# NOR_Flash_Storage_Module.net
KiCad netlist of a schematic drawn in EasyEDA
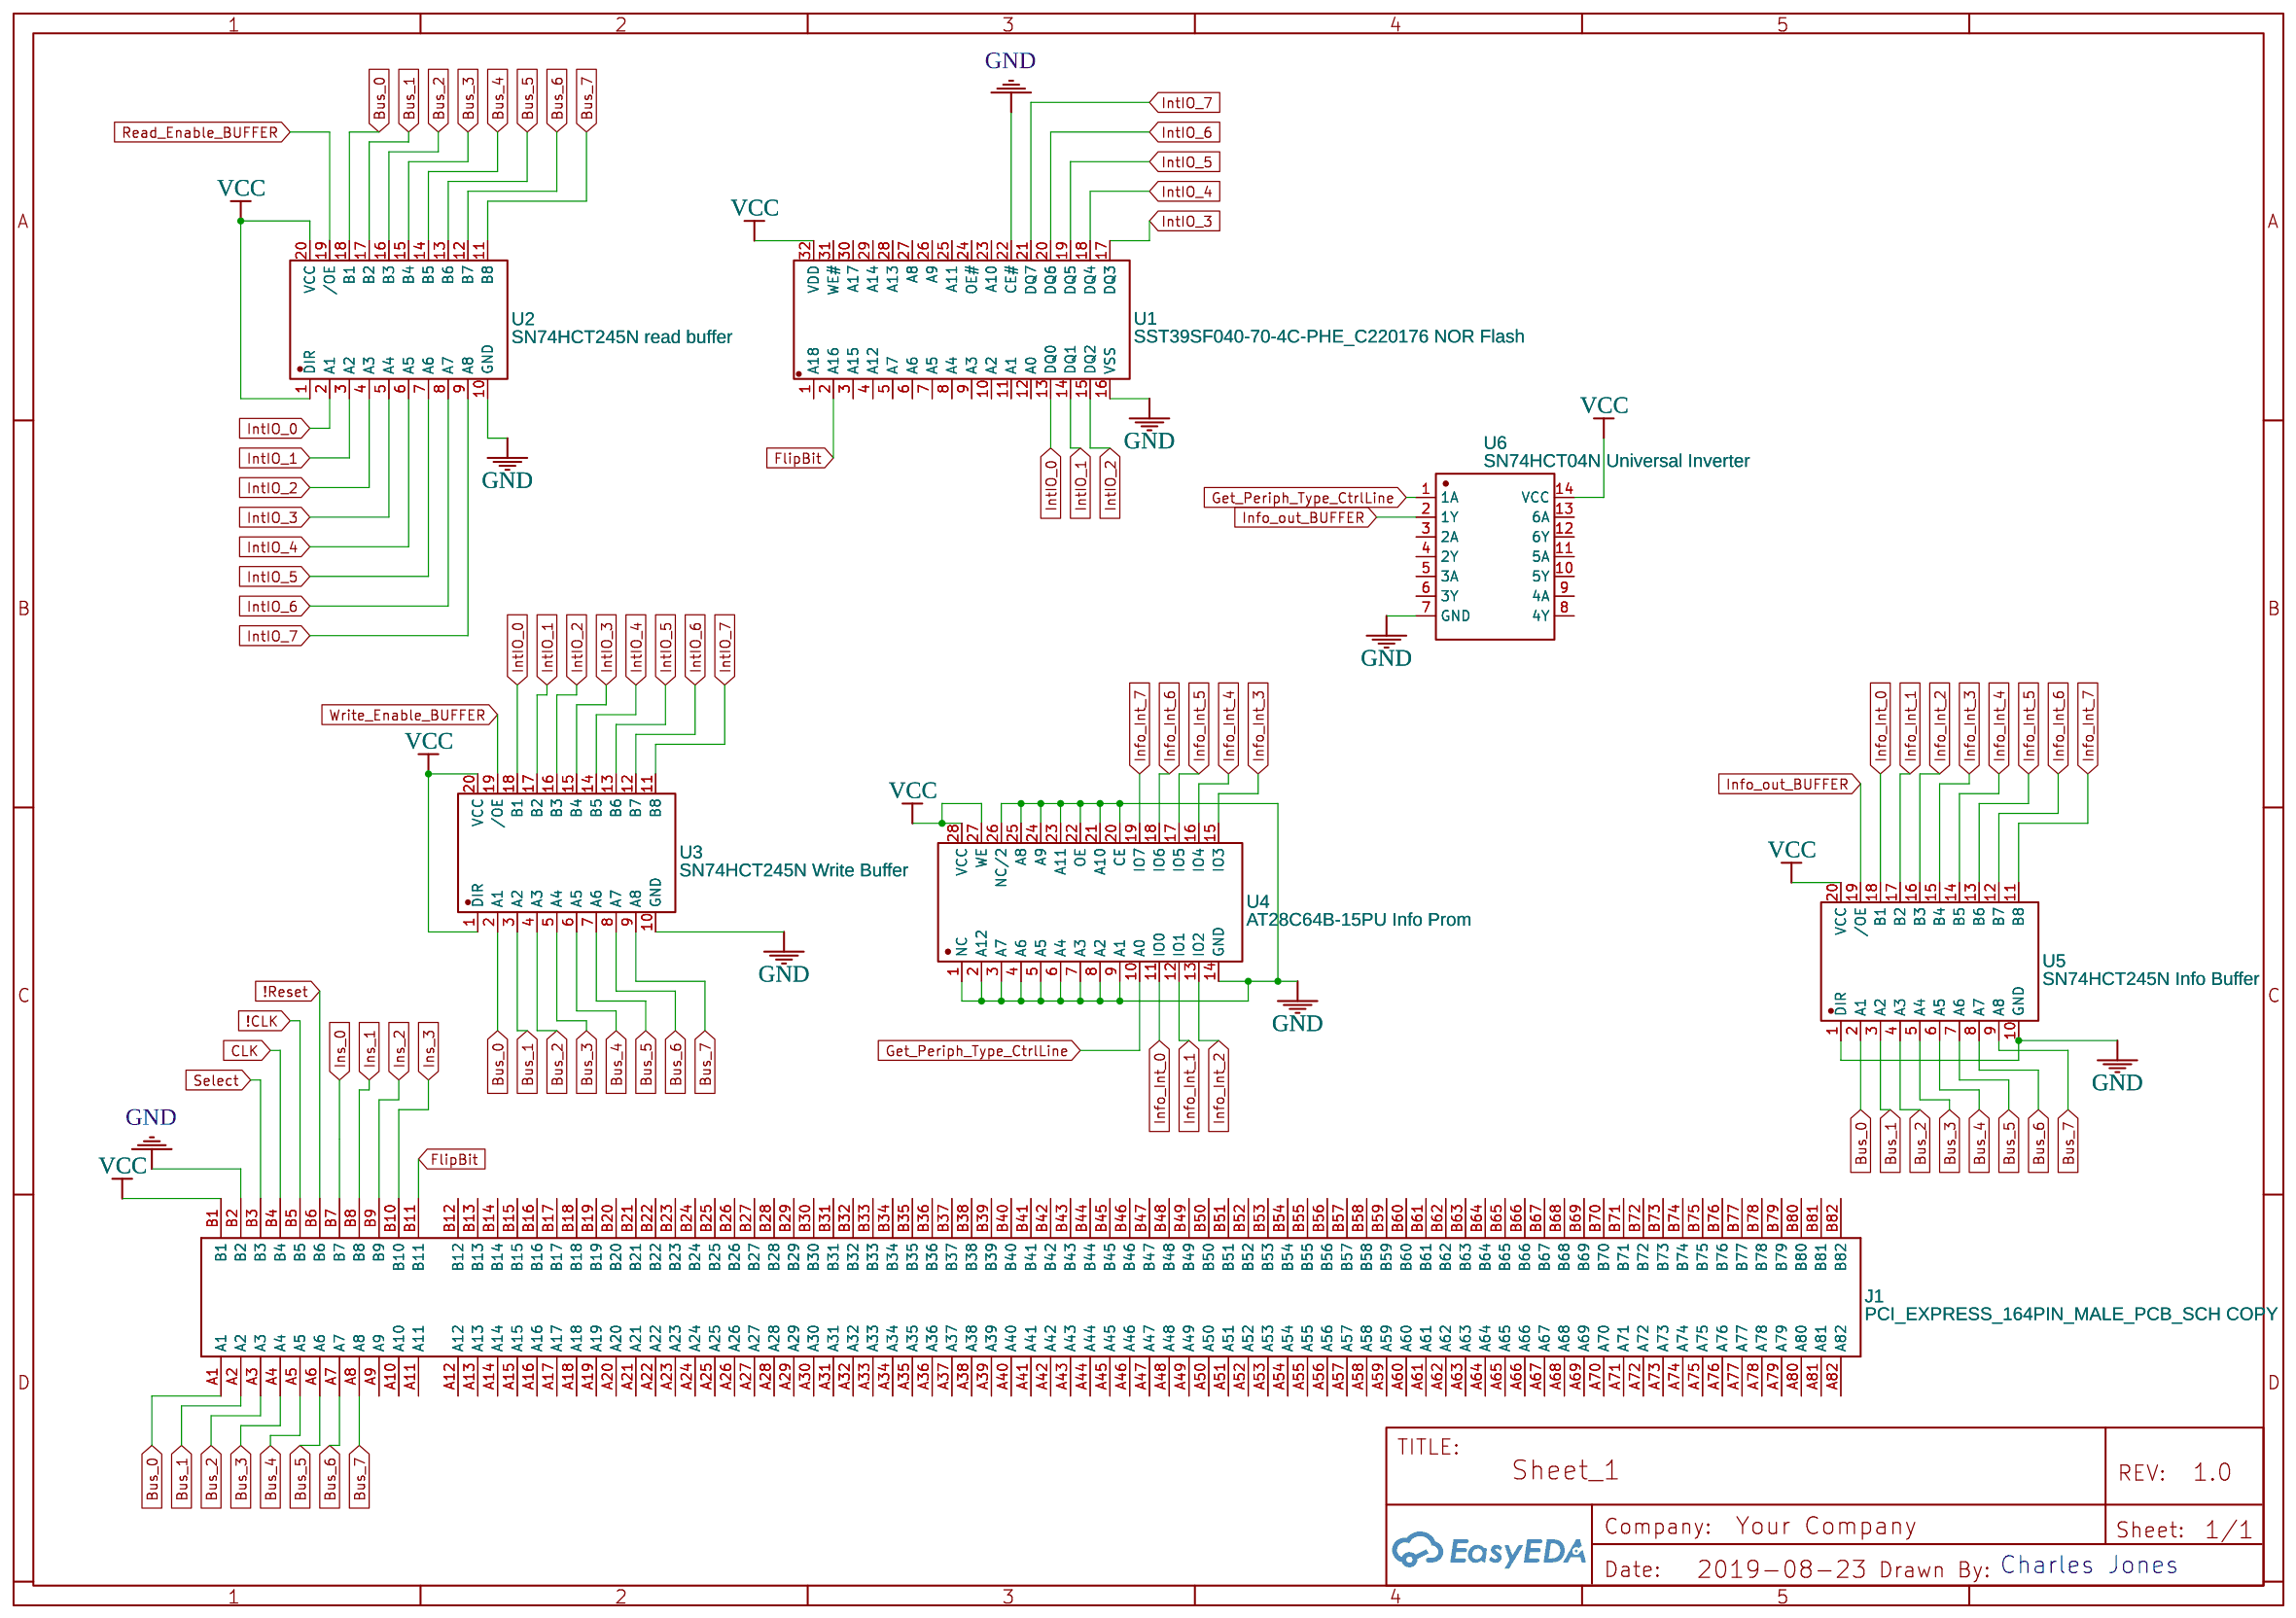
[diagram p0: schematic sheet]

(export (version "E")
  (design (tool "Eeschema 10.0.6"))
  (components
    (comp (ref "J1")
      (value "PCI_EXPRESS_164PIN_MALE_PCB_SCH COPY")
      (fields
        (field (name "BOM_Manufacturer Part") "PCI_EXPRESS_PCB")
        (field (name "BOM_Supplier Part") "undefined")
      )
      (libsource (lib "") (part "Unknown_435_695"))
    )
    (comp (ref "U1")
      (value "SST39SF040-70-4C-PHE_C220176 NOR Flash")
      (fields
        (field (name "BOM_Manufacturer Part") "SST39SF040-70-4C-PHE")
        (field (name "BOM_Supplier Part") "C220176")
      )
      (libsource (lib "") (part "Unknown_820_170"))
    )
    (comp (ref "U2")
      (value "SN74HCT245N read buffer")
      (fields
        (field (name "BOM_Manufacturer Part") "SN74HCT245N")
        (field (name "BOM_Supplier Part") "C133640")
      )
      (libsource (lib "") (part "Unknown_535_170"))
    )
    (comp (ref "U3")
      (value "SN74HCT245N Write Buffer")
      (fields
        (field (name "BOM_Manufacturer Part") "SN74HCT245N")
        (field (name "BOM_Supplier Part") "C133640")
      )
      (libsource (lib "") (part "Unknown_620_440"))
    )
    (comp (ref "U4")
      (value "AT28C64B-15PU Info Prom")
      (fields
        (field (name "BOM_Manufacturer Part") "AT28C64B-15PU")
        (field (name "BOM_Supplier Part") "C41982")
      )
      (libsource (lib "") (part "Unknown_885_465"))
    )
    (comp (ref "U5")
      (value "SN74HCT245N Info Buffer")
      (fields
        (field (name "BOM_Manufacturer Part") "SN74HCT245N")
        (field (name "BOM_Supplier Part") "C133640")
      )
      (libsource (lib "") (part "Unknown_1310_495"))
    )
    (comp (ref "U6") (value "SN74HCT04N Universal Inverter") (libsource (lib "") (part "Unknown_1090_290")))
  )
  (nets
    (net (code "1") (name "!CLK") (class "Default")
      (node (ref "J1") (pin "B5") (pinfunction "B5_B5") (pintype "unspecified"))
    )
    (net (code "2") (name "!Reset") (class "Default")
      (node (ref "J1") (pin "B6") (pinfunction "B6_B6") (pintype "unspecified"))
    )
    (net (code "3") (name "Bus_0") (class "Default")
      (node (ref "J1") (pin "A1") (pinfunction "A1_A1") (pintype "unspecified"))
      (node (ref "U2") (pin "18") (pinfunction "B1_18") (pintype "unspecified"))
      (node (ref "U3") (pin "2") (pinfunction "A1_2") (pintype "unspecified"))
      (node (ref "U5") (pin "2") (pinfunction "A1_2") (pintype "unspecified"))
    )
    (net (code "4") (name "Bus_1") (class "Default")
      (node (ref "J1") (pin "A2") (pinfunction "A2_A2") (pintype "unspecified"))
      (node (ref "U2") (pin "17") (pinfunction "B2_17") (pintype "unspecified"))
      (node (ref "U3") (pin "3") (pinfunction "A2_3") (pintype "unspecified"))
      (node (ref "U5") (pin "3") (pinfunction "A2_3") (pintype "unspecified"))
    )
    (net (code "5") (name "Bus_2") (class "Default")
      (node (ref "J1") (pin "A3") (pinfunction "A3_A3") (pintype "unspecified"))
      (node (ref "U2") (pin "16") (pinfunction "B3_16") (pintype "unspecified"))
      (node (ref "U3") (pin "4") (pinfunction "A3_4") (pintype "unspecified"))
      (node (ref "U5") (pin "4") (pinfunction "A3_4") (pintype "unspecified"))
    )
    (net (code "6") (name "Bus_3") (class "Default")
      (node (ref "J1") (pin "A4") (pinfunction "A4_A4") (pintype "unspecified"))
      (node (ref "U2") (pin "15") (pinfunction "B4_15") (pintype "unspecified"))
      (node (ref "U3") (pin "5") (pinfunction "A4_5") (pintype "unspecified"))
      (node (ref "U5") (pin "5") (pinfunction "A4_5") (pintype "unspecified"))
    )
    (net (code "7") (name "Bus_4") (class "Default")
      (node (ref "J1") (pin "A5") (pinfunction "A5_A5") (pintype "unspecified"))
      (node (ref "U2") (pin "14") (pinfunction "B5_14") (pintype "unspecified"))
      (node (ref "U3") (pin "6") (pinfunction "A5_6") (pintype "unspecified"))
      (node (ref "U5") (pin "6") (pinfunction "A5_6") (pintype "unspecified"))
    )
    (net (code "8") (name "Bus_5") (class "Default")
      (node (ref "J1") (pin "A6") (pinfunction "A6_A6") (pintype "unspecified"))
      (node (ref "U2") (pin "13") (pinfunction "B6_13") (pintype "unspecified"))
      (node (ref "U3") (pin "7") (pinfunction "A6_7") (pintype "unspecified"))
      (node (ref "U5") (pin "7") (pinfunction "A6_7") (pintype "unspecified"))
    )
    (net (code "9") (name "Bus_6") (class "Default")
      (node (ref "J1") (pin "A7") (pinfunction "A7_A7") (pintype "unspecified"))
      (node (ref "U2") (pin "12") (pinfunction "B7_12") (pintype "unspecified"))
      (node (ref "U3") (pin "8") (pinfunction "A7_8") (pintype "unspecified"))
      (node (ref "U5") (pin "8") (pinfunction "A7_8") (pintype "unspecified"))
    )
    (net (code "10") (name "Bus_7") (class "Default")
      (node (ref "J1") (pin "A8") (pinfunction "A8_A8") (pintype "unspecified"))
      (node (ref "U2") (pin "11") (pinfunction "B8_11") (pintype "unspecified"))
      (node (ref "U3") (pin "9") (pinfunction "A8_9") (pintype "unspecified"))
      (node (ref "U5") (pin "9") (pinfunction "A8_9") (pintype "unspecified"))
    )
    (net (code "11") (name "CLK") (class "Default")
      (node (ref "J1") (pin "B4") (pinfunction "B4_B4") (pintype "unspecified"))
    )
    (net (code "12") (name "FlipBit") (class "Default")
      (node (ref "J1") (pin "B11") (pinfunction "B11_B11") (pintype "unspecified"))
      (node (ref "U1") (pin "2") (pinfunction "A16_2") (pintype "unspecified"))
    )
    (net (code "13") (name "GND") (class "Default")
      (node (ref "J1") (pin "B2") (pinfunction "B2_B2") (pintype "unspecified"))
      (node (ref "U1") (pin "16") (pinfunction "VSS_16") (pintype "unspecified"))
      (node (ref "U1") (pin "22") (pinfunction "CE#_22") (pintype "unspecified"))
      (node (ref "U2") (pin "10") (pinfunction "GND_10") (pintype "unspecified"))
      (node (ref "U3") (pin "10") (pinfunction "GND_10") (pintype "unspecified"))
      (node (ref "U4") (pin "1") (pinfunction "NC_1") (pintype "unspecified"))
      (node (ref "U4") (pin "14") (pinfunction "GND_14") (pintype "unspecified"))
      (node (ref "U4") (pin "2") (pinfunction "A12_2") (pintype "unspecified"))
      (node (ref "U4") (pin "20") (pinfunction "CE_20") (pintype "unspecified"))
      (node (ref "U4") (pin "21") (pinfunction "A10_21") (pintype "unspecified"))
      (node (ref "U4") (pin "22") (pinfunction "OE_22") (pintype "unspecified"))
      (node (ref "U4") (pin "23") (pinfunction "A11_23") (pintype "unspecified"))
      (node (ref "U4") (pin "24") (pinfunction "A9_24") (pintype "unspecified"))
      (node (ref "U4") (pin "25") (pinfunction "A8_25") (pintype "unspecified"))
      (node (ref "U4") (pin "26") (pinfunction "NC/2_26") (pintype "unspecified"))
      (node (ref "U4") (pin "3") (pinfunction "A7_3") (pintype "unspecified"))
      (node (ref "U4") (pin "4") (pinfunction "A6_4") (pintype "unspecified"))
      (node (ref "U4") (pin "5") (pinfunction "A5_5") (pintype "unspecified"))
      (node (ref "U4") (pin "6") (pinfunction "A4_6") (pintype "unspecified"))
      (node (ref "U4") (pin "7") (pinfunction "A3_7") (pintype "unspecified"))
      (node (ref "U4") (pin "8") (pinfunction "A2_8") (pintype "unspecified"))
      (node (ref "U4") (pin "9") (pinfunction "A1_9") (pintype "unspecified"))
      (node (ref "U5") (pin "1") (pinfunction "DIR_1") (pintype "unspecified"))
      (node (ref "U5") (pin "10") (pinfunction "GND_10") (pintype "unspecified"))
      (node (ref "U6") (pin "7") (pinfunction "GND_7") (pintype "unspecified"))
    )
    (net (code "14") (name "Get_Periph_Type_CtrlLine") (class "Default")
      (node (ref "U4") (pin "10") (pinfunction "A0_10") (pintype "unspecified"))
      (node (ref "U6") (pin "1") (pinfunction "1A_1") (pintype "unspecified"))
    )
    (net (code "15") (name "Info_Int_0") (class "Default")
      (node (ref "U4") (pin "11") (pinfunction "IO0_11") (pintype "unspecified"))
      (node (ref "U5") (pin "18") (pinfunction "B1_18") (pintype "unspecified"))
    )
    (net (code "16") (name "Info_Int_1") (class "Default")
      (node (ref "U4") (pin "12") (pinfunction "IO1_12") (pintype "unspecified"))
      (node (ref "U5") (pin "17") (pinfunction "B2_17") (pintype "unspecified"))
    )
    (net (code "17") (name "Info_Int_2") (class "Default")
      (node (ref "U4") (pin "13") (pinfunction "IO2_13") (pintype "unspecified"))
      (node (ref "U5") (pin "16") (pinfunction "B3_16") (pintype "unspecified"))
    )
    (net (code "18") (name "Info_Int_3") (class "Default")
      (node (ref "U4") (pin "15") (pinfunction "IO3_15") (pintype "unspecified"))
      (node (ref "U5") (pin "15") (pinfunction "B4_15") (pintype "unspecified"))
    )
    (net (code "19") (name "Info_Int_4") (class "Default")
      (node (ref "U4") (pin "16") (pinfunction "IO4_16") (pintype "unspecified"))
      (node (ref "U5") (pin "14") (pinfunction "B5_14") (pintype "unspecified"))
    )
    (net (code "20") (name "Info_Int_5") (class "Default")
      (node (ref "U4") (pin "17") (pinfunction "IO5_17") (pintype "unspecified"))
      (node (ref "U5") (pin "13") (pinfunction "B6_13") (pintype "unspecified"))
    )
    (net (code "21") (name "Info_Int_6") (class "Default")
      (node (ref "U4") (pin "18") (pinfunction "IO6_18") (pintype "unspecified"))
      (node (ref "U5") (pin "12") (pinfunction "B7_12") (pintype "unspecified"))
    )
    (net (code "22") (name "Info_Int_7") (class "Default")
      (node (ref "U4") (pin "19") (pinfunction "IO7_19") (pintype "unspecified"))
      (node (ref "U5") (pin "11") (pinfunction "B8_11") (pintype "unspecified"))
    )
    (net (code "23") (name "Info_out_BUFFER") (class "Default")
      (node (ref "U5") (pin "19") (pinfunction "/OE_19") (pintype "unspecified"))
      (node (ref "U6") (pin "2") (pinfunction "1Y_2") (pintype "unspecified"))
    )
    (net (code "24") (name "Ins_0") (class "Default")
      (node (ref "J1") (pin "B7") (pinfunction "B7_B7") (pintype "unspecified"))
    )
    (net (code "25") (name "Ins_1") (class "Default")
      (node (ref "J1") (pin "B8") (pinfunction "B8_B8") (pintype "unspecified"))
    )
    (net (code "26") (name "Ins_2") (class "Default")
      (node (ref "J1") (pin "B9") (pinfunction "B9_B9") (pintype "unspecified"))
    )
    (net (code "27") (name "Ins_3") (class "Default")
      (node (ref "J1") (pin "B10") (pinfunction "B10_B10") (pintype "unspecified"))
    )
    (net (code "28") (name "IntIO_0") (class "Default")
      (node (ref "U1") (pin "13") (pinfunction "DQ0_13") (pintype "unspecified"))
      (node (ref "U2") (pin "2") (pinfunction "A1_2") (pintype "unspecified"))
      (node (ref "U3") (pin "18") (pinfunction "B1_18") (pintype "unspecified"))
    )
    (net (code "29") (name "IntIO_1") (class "Default")
      (node (ref "U1") (pin "14") (pinfunction "DQ1_14") (pintype "unspecified"))
      (node (ref "U2") (pin "3") (pinfunction "A2_3") (pintype "unspecified"))
      (node (ref "U3") (pin "17") (pinfunction "B2_17") (pintype "unspecified"))
    )
    (net (code "30") (name "IntIO_2") (class "Default")
      (node (ref "U1") (pin "15") (pinfunction "DQ2_15") (pintype "unspecified"))
      (node (ref "U2") (pin "4") (pinfunction "A3_4") (pintype "unspecified"))
      (node (ref "U3") (pin "16") (pinfunction "B3_16") (pintype "unspecified"))
    )
    (net (code "31") (name "IntIO_3") (class "Default")
      (node (ref "U1") (pin "17") (pinfunction "DQ3_17") (pintype "unspecified"))
      (node (ref "U2") (pin "5") (pinfunction "A4_5") (pintype "unspecified"))
      (node (ref "U3") (pin "15") (pinfunction "B4_15") (pintype "unspecified"))
    )
    (net (code "32") (name "IntIO_4") (class "Default")
      (node (ref "U1") (pin "18") (pinfunction "DQ4_18") (pintype "unspecified"))
      (node (ref "U2") (pin "6") (pinfunction "A5_6") (pintype "unspecified"))
      (node (ref "U3") (pin "14") (pinfunction "B5_14") (pintype "unspecified"))
    )
    (net (code "33") (name "IntIO_5") (class "Default")
      (node (ref "U1") (pin "19") (pinfunction "DQ5_19") (pintype "unspecified"))
      (node (ref "U2") (pin "7") (pinfunction "A6_7") (pintype "unspecified"))
      (node (ref "U3") (pin "13") (pinfunction "B6_13") (pintype "unspecified"))
    )
    (net (code "34") (name "IntIO_6") (class "Default")
      (node (ref "U1") (pin "20") (pinfunction "DQ6_20") (pintype "unspecified"))
      (node (ref "U2") (pin "8") (pinfunction "A7_8") (pintype "unspecified"))
      (node (ref "U3") (pin "12") (pinfunction "B7_12") (pintype "unspecified"))
    )
    (net (code "35") (name "IntIO_7") (class "Default")
      (node (ref "U1") (pin "21") (pinfunction "DQ7_21") (pintype "unspecified"))
      (node (ref "U2") (pin "9") (pinfunction "A8_9") (pintype "unspecified"))
      (node (ref "U3") (pin "11") (pinfunction "B8_11") (pintype "unspecified"))
    )
    (net (code "36") (name "Read_Enable_BUFFER") (class "Default")
      (node (ref "U2") (pin "19") (pinfunction "/OE_19") (pintype "unspecified"))
    )
    (net (code "37") (name "Select") (class "Default")
      (node (ref "J1") (pin "B3") (pinfunction "B3_B3") (pintype "unspecified"))
    )
    (net (code "38") (name "VCC") (class "Default")
      (node (ref "J1") (pin "B1") (pinfunction "B1_B1") (pintype "unspecified"))
      (node (ref "U1") (pin "32") (pinfunction "VDD_32") (pintype "unspecified"))
      (node (ref "U2") (pin "1") (pinfunction "DIR_1") (pintype "unspecified"))
      (node (ref "U2") (pin "20") (pinfunction "VCC_20") (pintype "unspecified"))
      (node (ref "U3") (pin "1") (pinfunction "DIR_1") (pintype "unspecified"))
      (node (ref "U3") (pin "20") (pinfunction "VCC_20") (pintype "unspecified"))
      (node (ref "U4") (pin "27") (pinfunction "WE_27") (pintype "unspecified"))
      (node (ref "U4") (pin "28") (pinfunction "VCC_28") (pintype "unspecified"))
      (node (ref "U5") (pin "20") (pinfunction "VCC_20") (pintype "unspecified"))
      (node (ref "U6") (pin "14") (pinfunction "VCC_14") (pintype "unspecified"))
    )
    (net (code "39") (name "Write_Enable_BUFFER") (class "Default")
      (node (ref "U3") (pin "19") (pinfunction "/OE_19") (pintype "unspecified"))
    )
    (net (code "40") (name "unconnected-(J1-PadA9)") (class "Default")
      (node (ref "J1") (pin "A9") (pinfunction "A9_A9") (pintype "unspecified"))
    )
    (net (code "41") (name "unconnected-(J1-PadA10)") (class "Default")
      (node (ref "J1") (pin "A10") (pinfunction "A10_A10") (pintype "unspecified"))
    )
    (net (code "42") (name "unconnected-(J1-PadA11)") (class "Default")
      (node (ref "J1") (pin "A11") (pinfunction "A11_A11") (pintype "unspecified"))
    )
    (net (code "43") (name "unconnected-(J1-PadA12)") (class "Default")
      (node (ref "J1") (pin "A12") (pinfunction "A12_A12") (pintype "unspecified"))
    )
    (net (code "44") (name "unconnected-(J1-PadA13)") (class "Default")
      (node (ref "J1") (pin "A13") (pinfunction "A13_A13") (pintype "unspecified"))
    )
    (net (code "45") (name "unconnected-(J1-PadA14)") (class "Default")
      (node (ref "J1") (pin "A14") (pinfunction "A14_A14") (pintype "unspecified"))
    )
    (net (code "46") (name "unconnected-(J1-PadA15)") (class "Default")
      (node (ref "J1") (pin "A15") (pinfunction "A15_A15") (pintype "unspecified"))
    )
    (net (code "47") (name "unconnected-(J1-PadA16)") (class "Default")
      (node (ref "J1") (pin "A16") (pinfunction "A16_A16") (pintype "unspecified"))
    )
    (net (code "48") (name "unconnected-(J1-PadA17)") (class "Default")
      (node (ref "J1") (pin "A17") (pinfunction "A17_A17") (pintype "unspecified"))
    )
    (net (code "49") (name "unconnected-(J1-PadA18)") (class "Default")
      (node (ref "J1") (pin "A18") (pinfunction "A18_A18") (pintype "unspecified"))
    )
    (net (code "50") (name "unconnected-(J1-PadA19)") (class "Default")
      (node (ref "J1") (pin "A19") (pinfunction "A19_A19") (pintype "unspecified"))
    )
    (net (code "51") (name "unconnected-(J1-PadA20)") (class "Default")
      (node (ref "J1") (pin "A20") (pinfunction "A20_A20") (pintype "unspecified"))
    )
    (net (code "52") (name "unconnected-(J1-PadA21)") (class "Default")
      (node (ref "J1") (pin "A21") (pinfunction "A21_A21") (pintype "unspecified"))
    )
    (net (code "53") (name "unconnected-(J1-PadA22)") (class "Default")
      (node (ref "J1") (pin "A22") (pinfunction "A22_A22") (pintype "unspecified"))
    )
    (net (code "54") (name "unconnected-(J1-PadA23)") (class "Default")
      (node (ref "J1") (pin "A23") (pinfunction "A23_A23") (pintype "unspecified"))
    )
    (net (code "55") (name "unconnected-(J1-PadA24)") (class "Default")
      (node (ref "J1") (pin "A24") (pinfunction "A24_A24") (pintype "unspecified"))
    )
    (net (code "56") (name "unconnected-(J1-PadA25)") (class "Default")
      (node (ref "J1") (pin "A25") (pinfunction "A25_A25") (pintype "unspecified"))
    )
    (net (code "57") (name "unconnected-(J1-PadA26)") (class "Default")
      (node (ref "J1") (pin "A26") (pinfunction "A26_A26") (pintype "unspecified"))
    )
    (net (code "58") (name "unconnected-(J1-PadA27)") (class "Default")
      (node (ref "J1") (pin "A27") (pinfunction "A27_A27") (pintype "unspecified"))
    )
    (net (code "59") (name "unconnected-(J1-PadA28)") (class "Default")
      (node (ref "J1") (pin "A28") (pinfunction "A28_A28") (pintype "unspecified"))
    )
    (net (code "60") (name "unconnected-(J1-PadA29)") (class "Default")
      (node (ref "J1") (pin "A29") (pinfunction "A29_A29") (pintype "unspecified"))
    )
    (net (code "61") (name "unconnected-(J1-PadA30)") (class "Default")
      (node (ref "J1") (pin "A30") (pinfunction "A30_A30") (pintype "unspecified"))
    )
    (net (code "62") (name "unconnected-(J1-PadA31)") (class "Default")
      (node (ref "J1") (pin "A31") (pinfunction "A31_A31") (pintype "unspecified"))
    )
    (net (code "63") (name "unconnected-(J1-PadA32)") (class "Default")
      (node (ref "J1") (pin "A32") (pinfunction "A32_A32") (pintype "unspecified"))
    )
    (net (code "64") (name "unconnected-(J1-PadA33)") (class "Default")
      (node (ref "J1") (pin "A33") (pinfunction "A33_A33") (pintype "unspecified"))
    )
    (net (code "65") (name "unconnected-(J1-PadA34)") (class "Default")
      (node (ref "J1") (pin "A34") (pinfunction "A34_A34") (pintype "unspecified"))
    )
    (net (code "66") (name "unconnected-(J1-PadA35)") (class "Default")
      (node (ref "J1") (pin "A35") (pinfunction "A35_A35") (pintype "unspecified"))
    )
    (net (code "67") (name "unconnected-(J1-PadA36)") (class "Default")
      (node (ref "J1") (pin "A36") (pinfunction "A36_A36") (pintype "unspecified"))
    )
    (net (code "68") (name "unconnected-(J1-PadA37)") (class "Default")
      (node (ref "J1") (pin "A37") (pinfunction "A37_A37") (pintype "unspecified"))
    )
    (net (code "69") (name "unconnected-(J1-PadA38)") (class "Default")
      (node (ref "J1") (pin "A38") (pinfunction "A38_A38") (pintype "unspecified"))
    )
    (net (code "70") (name "unconnected-(J1-PadA39)") (class "Default")
      (node (ref "J1") (pin "A39") (pinfunction "A39_A39") (pintype "unspecified"))
    )
    (net (code "71") (name "unconnected-(J1-PadA40)") (class "Default")
      (node (ref "J1") (pin "A40") (pinfunction "A40_A40") (pintype "unspecified"))
    )
    (net (code "72") (name "unconnected-(J1-PadA41)") (class "Default")
      (node (ref "J1") (pin "A41") (pinfunction "A41_A41") (pintype "unspecified"))
    )
    (net (code "73") (name "unconnected-(J1-PadA42)") (class "Default")
      (node (ref "J1") (pin "A42") (pinfunction "A42_A42") (pintype "unspecified"))
    )
    (net (code "74") (name "unconnected-(J1-PadA43)") (class "Default")
      (node (ref "J1") (pin "A43") (pinfunction "A43_A43") (pintype "unspecified"))
    )
    (net (code "75") (name "unconnected-(J1-PadA44)") (class "Default")
      (node (ref "J1") (pin "A44") (pinfunction "A44_A44") (pintype "unspecified"))
    )
    (net (code "76") (name "unconnected-(J1-PadA45)") (class "Default")
      (node (ref "J1") (pin "A45") (pinfunction "A45_A45") (pintype "unspecified"))
    )
    (net (code "77") (name "unconnected-(J1-PadA46)") (class "Default")
      (node (ref "J1") (pin "A46") (pinfunction "A46_A46") (pintype "unspecified"))
    )
    (net (code "78") (name "unconnected-(J1-PadA47)") (class "Default")
      (node (ref "J1") (pin "A47") (pinfunction "A47_A47") (pintype "unspecified"))
    )
    (net (code "79") (name "unconnected-(J1-PadA48)") (class "Default")
      (node (ref "J1") (pin "A48") (pinfunction "A48_A48") (pintype "unspecified"))
    )
    (net (code "80") (name "unconnected-(J1-PadA49)") (class "Default")
      (node (ref "J1") (pin "A49") (pinfunction "A49_A49") (pintype "unspecified"))
    )
    (net (code "81") (name "unconnected-(J1-PadA50)") (class "Default")
      (node (ref "J1") (pin "A50") (pinfunction "A50_A50") (pintype "unspecified"))
    )
    (net (code "82") (name "unconnected-(J1-PadA51)") (class "Default")
      (node (ref "J1") (pin "A51") (pinfunction "A51_A51") (pintype "unspecified"))
    )
    (net (code "83") (name "unconnected-(J1-PadA52)") (class "Default")
      (node (ref "J1") (pin "A52") (pinfunction "A52_A52") (pintype "unspecified"))
    )
    (net (code "84") (name "unconnected-(J1-PadA53)") (class "Default")
      (node (ref "J1") (pin "A53") (pinfunction "A53_A53") (pintype "unspecified"))
    )
    (net (code "85") (name "unconnected-(J1-PadA54)") (class "Default")
      (node (ref "J1") (pin "A54") (pinfunction "A54_A54") (pintype "unspecified"))
    )
    (net (code "86") (name "unconnected-(J1-PadA55)") (class "Default")
      (node (ref "J1") (pin "A55") (pinfunction "A55_A55") (pintype "unspecified"))
    )
    (net (code "87") (name "unconnected-(J1-PadA56)") (class "Default")
      (node (ref "J1") (pin "A56") (pinfunction "A56_A56") (pintype "unspecified"))
    )
    (net (code "88") (name "unconnected-(J1-PadA57)") (class "Default")
      (node (ref "J1") (pin "A57") (pinfunction "A57_A57") (pintype "unspecified"))
    )
    (net (code "89") (name "unconnected-(J1-PadA58)") (class "Default")
      (node (ref "J1") (pin "A58") (pinfunction "A58_A58") (pintype "unspecified"))
    )
    (net (code "90") (name "unconnected-(J1-PadA59)") (class "Default")
      (node (ref "J1") (pin "A59") (pinfunction "A59_A59") (pintype "unspecified"))
    )
    (net (code "91") (name "unconnected-(J1-PadA60)") (class "Default")
      (node (ref "J1") (pin "A60") (pinfunction "A60_A60") (pintype "unspecified"))
    )
    (net (code "92") (name "unconnected-(J1-PadA61)") (class "Default")
      (node (ref "J1") (pin "A61") (pinfunction "A61_A61") (pintype "unspecified"))
    )
    (net (code "93") (name "unconnected-(J1-PadA62)") (class "Default")
      (node (ref "J1") (pin "A62") (pinfunction "A62_A62") (pintype "unspecified"))
    )
    (net (code "94") (name "unconnected-(J1-PadA63)") (class "Default")
      (node (ref "J1") (pin "A63") (pinfunction "A63_A63") (pintype "unspecified"))
    )
    (net (code "95") (name "unconnected-(J1-PadA64)") (class "Default")
      (node (ref "J1") (pin "A64") (pinfunction "A64_A64") (pintype "unspecified"))
    )
    (net (code "96") (name "unconnected-(J1-PadA65)") (class "Default")
      (node (ref "J1") (pin "A65") (pinfunction "A65_A65") (pintype "unspecified"))
    )
    (net (code "97") (name "unconnected-(J1-PadA66)") (class "Default")
      (node (ref "J1") (pin "A66") (pinfunction "A66_A66") (pintype "unspecified"))
    )
    (net (code "98") (name "unconnected-(J1-PadA67)") (class "Default")
      (node (ref "J1") (pin "A67") (pinfunction "A67_A67") (pintype "unspecified"))
    )
    (net (code "99") (name "unconnected-(J1-PadA68)") (class "Default")
      (node (ref "J1") (pin "A68") (pinfunction "A68_A68") (pintype "unspecified"))
    )
    (net (code "100") (name "unconnected-(J1-PadA69)") (class "Default")
      (node (ref "J1") (pin "A69") (pinfunction "A69_A69") (pintype "unspecified"))
    )
    (net (code "101") (name "unconnected-(J1-PadA70)") (class "Default")
      (node (ref "J1") (pin "A70") (pinfunction "A70_A70") (pintype "unspecified"))
    )
    (net (code "102") (name "unconnected-(J1-PadA71)") (class "Default")
      (node (ref "J1") (pin "A71") (pinfunction "A71_A71") (pintype "unspecified"))
    )
    (net (code "103") (name "unconnected-(J1-PadA72)") (class "Default")
      (node (ref "J1") (pin "A72") (pinfunction "A72_A72") (pintype "unspecified"))
    )
    (net (code "104") (name "unconnected-(J1-PadA73)") (class "Default")
      (node (ref "J1") (pin "A73") (pinfunction "A73_A73") (pintype "unspecified"))
    )
    (net (code "105") (name "unconnected-(J1-PadA74)") (class "Default")
      (node (ref "J1") (pin "A74") (pinfunction "A74_A74") (pintype "unspecified"))
    )
    (net (code "106") (name "unconnected-(J1-PadA75)") (class "Default")
      (node (ref "J1") (pin "A75") (pinfunction "A75_A75") (pintype "unspecified"))
    )
    (net (code "107") (name "unconnected-(J1-PadA76)") (class "Default")
      (node (ref "J1") (pin "A76") (pinfunction "A76_A76") (pintype "unspecified"))
    )
    (net (code "108") (name "unconnected-(J1-PadA77)") (class "Default")
      (node (ref "J1") (pin "A77") (pinfunction "A77_A77") (pintype "unspecified"))
    )
    (net (code "109") (name "unconnected-(J1-PadA78)") (class "Default")
      (node (ref "J1") (pin "A78") (pinfunction "A78_A78") (pintype "unspecified"))
    )
    (net (code "110") (name "unconnected-(J1-PadA79)") (class "Default")
      (node (ref "J1") (pin "A79") (pinfunction "A79_A79") (pintype "unspecified"))
    )
    (net (code "111") (name "unconnected-(J1-PadA80)") (class "Default")
      (node (ref "J1") (pin "A80") (pinfunction "A80_A80") (pintype "unspecified"))
    )
    (net (code "112") (name "unconnected-(J1-PadA81)") (class "Default")
      (node (ref "J1") (pin "A81") (pinfunction "A81_A81") (pintype "unspecified"))
    )
    (net (code "113") (name "unconnected-(J1-PadA82)") (class "Default")
      (node (ref "J1") (pin "A82") (pinfunction "A82_A82") (pintype "unspecified"))
    )
    (net (code "114") (name "unconnected-(J1-PadB12)") (class "Default")
      (node (ref "J1") (pin "B12") (pinfunction "B12_B12") (pintype "unspecified"))
    )
    (net (code "115") (name "unconnected-(J1-PadB13)") (class "Default")
      (node (ref "J1") (pin "B13") (pinfunction "B13_B13") (pintype "unspecified"))
    )
    (net (code "116") (name "unconnected-(J1-PadB14)") (class "Default")
      (node (ref "J1") (pin "B14") (pinfunction "B14_B14") (pintype "unspecified"))
    )
    (net (code "117") (name "unconnected-(J1-PadB15)") (class "Default")
      (node (ref "J1") (pin "B15") (pinfunction "B15_B15") (pintype "unspecified"))
    )
    (net (code "118") (name "unconnected-(J1-PadB16)") (class "Default")
      (node (ref "J1") (pin "B16") (pinfunction "B16_B16") (pintype "unspecified"))
    )
    (net (code "119") (name "unconnected-(J1-PadB17)") (class "Default")
      (node (ref "J1") (pin "B17") (pinfunction "B17_B17") (pintype "unspecified"))
    )
    (net (code "120") (name "unconnected-(J1-PadB18)") (class "Default")
      (node (ref "J1") (pin "B18") (pinfunction "B18_B18") (pintype "unspecified"))
    )
    (net (code "121") (name "unconnected-(J1-PadB19)") (class "Default")
      (node (ref "J1") (pin "B19") (pinfunction "B19_B19") (pintype "unspecified"))
    )
    (net (code "122") (name "unconnected-(J1-PadB20)") (class "Default")
      (node (ref "J1") (pin "B20") (pinfunction "B20_B20") (pintype "unspecified"))
    )
    (net (code "123") (name "unconnected-(J1-PadB21)") (class "Default")
      (node (ref "J1") (pin "B21") (pinfunction "B21_B21") (pintype "unspecified"))
    )
    (net (code "124") (name "unconnected-(J1-PadB22)") (class "Default")
      (node (ref "J1") (pin "B22") (pinfunction "B22_B22") (pintype "unspecified"))
    )
    (net (code "125") (name "unconnected-(J1-PadB23)") (class "Default")
      (node (ref "J1") (pin "B23") (pinfunction "B23_B23") (pintype "unspecified"))
    )
    (net (code "126") (name "unconnected-(J1-PadB24)") (class "Default")
      (node (ref "J1") (pin "B24") (pinfunction "B24_B24") (pintype "unspecified"))
    )
    (net (code "127") (name "unconnected-(J1-PadB25)") (class "Default")
      (node (ref "J1") (pin "B25") (pinfunction "B25_B25") (pintype "unspecified"))
    )
    (net (code "128") (name "unconnected-(J1-PadB26)") (class "Default")
      (node (ref "J1") (pin "B26") (pinfunction "B26_B26") (pintype "unspecified"))
    )
    (net (code "129") (name "unconnected-(J1-PadB27)") (class "Default")
      (node (ref "J1") (pin "B27") (pinfunction "B27_B27") (pintype "unspecified"))
    )
    (net (code "130") (name "unconnected-(J1-PadB28)") (class "Default")
      (node (ref "J1") (pin "B28") (pinfunction "B28_B28") (pintype "unspecified"))
    )
    (net (code "131") (name "unconnected-(J1-PadB29)") (class "Default")
      (node (ref "J1") (pin "B29") (pinfunction "B29_B29") (pintype "unspecified"))
    )
    (net (code "132") (name "unconnected-(J1-PadB30)") (class "Default")
      (node (ref "J1") (pin "B30") (pinfunction "B30_B30") (pintype "unspecified"))
    )
    (net (code "133") (name "unconnected-(J1-PadB31)") (class "Default")
      (node (ref "J1") (pin "B31") (pinfunction "B31_B31") (pintype "unspecified"))
    )
    (net (code "134") (name "unconnected-(J1-PadB32)") (class "Default")
      (node (ref "J1") (pin "B32") (pinfunction "B32_B32") (pintype "unspecified"))
    )
    (net (code "135") (name "unconnected-(J1-PadB33)") (class "Default")
      (node (ref "J1") (pin "B33") (pinfunction "B33_B33") (pintype "unspecified"))
    )
    (net (code "136") (name "unconnected-(J1-PadB34)") (class "Default")
      (node (ref "J1") (pin "B34") (pinfunction "B34_B34") (pintype "unspecified"))
    )
    (net (code "137") (name "unconnected-(J1-PadB35)") (class "Default")
      (node (ref "J1") (pin "B35") (pinfunction "B35_B35") (pintype "unspecified"))
    )
    (net (code "138") (name "unconnected-(J1-PadB36)") (class "Default")
      (node (ref "J1") (pin "B36") (pinfunction "B36_B36") (pintype "unspecified"))
    )
    (net (code "139") (name "unconnected-(J1-PadB37)") (class "Default")
      (node (ref "J1") (pin "B37") (pinfunction "B37_B37") (pintype "unspecified"))
    )
    (net (code "140") (name "unconnected-(J1-PadB38)") (class "Default")
      (node (ref "J1") (pin "B38") (pinfunction "B38_B38") (pintype "unspecified"))
    )
    (net (code "141") (name "unconnected-(J1-PadB39)") (class "Default")
      (node (ref "J1") (pin "B39") (pinfunction "B39_B39") (pintype "unspecified"))
    )
    (net (code "142") (name "unconnected-(J1-PadB40)") (class "Default")
      (node (ref "J1") (pin "B40") (pinfunction "B40_B40") (pintype "unspecified"))
    )
    (net (code "143") (name "unconnected-(J1-PadB41)") (class "Default")
      (node (ref "J1") (pin "B41") (pinfunction "B41_B41") (pintype "unspecified"))
    )
    (net (code "144") (name "unconnected-(J1-PadB42)") (class "Default")
      (node (ref "J1") (pin "B42") (pinfunction "B42_B42") (pintype "unspecified"))
    )
    (net (code "145") (name "unconnected-(J1-PadB43)") (class "Default")
      (node (ref "J1") (pin "B43") (pinfunction "B43_B43") (pintype "unspecified"))
    )
    (net (code "146") (name "unconnected-(J1-PadB44)") (class "Default")
      (node (ref "J1") (pin "B44") (pinfunction "B44_B44") (pintype "unspecified"))
    )
    (net (code "147") (name "unconnected-(J1-PadB45)") (class "Default")
      (node (ref "J1") (pin "B45") (pinfunction "B45_B45") (pintype "unspecified"))
    )
    (net (code "148") (name "unconnected-(J1-PadB46)") (class "Default")
      (node (ref "J1") (pin "B46") (pinfunction "B46_B46") (pintype "unspecified"))
    )
    (net (code "149") (name "unconnected-(J1-PadB47)") (class "Default")
      (node (ref "J1") (pin "B47") (pinfunction "B47_B47") (pintype "unspecified"))
    )
    (net (code "150") (name "unconnected-(J1-PadB48)") (class "Default")
      (node (ref "J1") (pin "B48") (pinfunction "B48_B48") (pintype "unspecified"))
    )
    (net (code "151") (name "unconnected-(J1-PadB49)") (class "Default")
      (node (ref "J1") (pin "B49") (pinfunction "B49_B49") (pintype "unspecified"))
    )
    (net (code "152") (name "unconnected-(J1-PadB50)") (class "Default")
      (node (ref "J1") (pin "B50") (pinfunction "B50_B50") (pintype "unspecified"))
    )
    (net (code "153") (name "unconnected-(J1-PadB51)") (class "Default")
      (node (ref "J1") (pin "B51") (pinfunction "B51_B51") (pintype "unspecified"))
    )
    (net (code "154") (name "unconnected-(J1-PadB52)") (class "Default")
      (node (ref "J1") (pin "B52") (pinfunction "B52_B52") (pintype "unspecified"))
    )
    (net (code "155") (name "unconnected-(J1-PadB53)") (class "Default")
      (node (ref "J1") (pin "B53") (pinfunction "B53_B53") (pintype "unspecified"))
    )
    (net (code "156") (name "unconnected-(J1-PadB54)") (class "Default")
      (node (ref "J1") (pin "B54") (pinfunction "B54_B54") (pintype "unspecified"))
    )
    (net (code "157") (name "unconnected-(J1-PadB55)") (class "Default")
      (node (ref "J1") (pin "B55") (pinfunction "B55_B55") (pintype "unspecified"))
    )
    (net (code "158") (name "unconnected-(J1-PadB56)") (class "Default")
      (node (ref "J1") (pin "B56") (pinfunction "B56_B56") (pintype "unspecified"))
    )
    (net (code "159") (name "unconnected-(J1-PadB57)") (class "Default")
      (node (ref "J1") (pin "B57") (pinfunction "B57_B57") (pintype "unspecified"))
    )
    (net (code "160") (name "unconnected-(J1-PadB58)") (class "Default")
      (node (ref "J1") (pin "B58") (pinfunction "B58_B58") (pintype "unspecified"))
    )
    (net (code "161") (name "unconnected-(J1-PadB59)") (class "Default")
      (node (ref "J1") (pin "B59") (pinfunction "B59_B59") (pintype "unspecified"))
    )
    (net (code "162") (name "unconnected-(J1-PadB60)") (class "Default")
      (node (ref "J1") (pin "B60") (pinfunction "B60_B60") (pintype "unspecified"))
    )
    (net (code "163") (name "unconnected-(J1-PadB61)") (class "Default")
      (node (ref "J1") (pin "B61") (pinfunction "B61_B61") (pintype "unspecified"))
    )
    (net (code "164") (name "unconnected-(J1-PadB62)") (class "Default")
      (node (ref "J1") (pin "B62") (pinfunction "B62_B62") (pintype "unspecified"))
    )
    (net (code "165") (name "unconnected-(J1-PadB63)") (class "Default")
      (node (ref "J1") (pin "B63") (pinfunction "B63_B63") (pintype "unspecified"))
    )
    (net (code "166") (name "unconnected-(J1-PadB64)") (class "Default")
      (node (ref "J1") (pin "B64") (pinfunction "B64_B64") (pintype "unspecified"))
    )
    (net (code "167") (name "unconnected-(J1-PadB65)") (class "Default")
      (node (ref "J1") (pin "B65") (pinfunction "B65_B65") (pintype "unspecified"))
    )
    (net (code "168") (name "unconnected-(J1-PadB66)") (class "Default")
      (node (ref "J1") (pin "B66") (pinfunction "B66_B66") (pintype "unspecified"))
    )
    (net (code "169") (name "unconnected-(J1-PadB67)") (class "Default")
      (node (ref "J1") (pin "B67") (pinfunction "B67_B67") (pintype "unspecified"))
    )
    (net (code "170") (name "unconnected-(J1-PadB68)") (class "Default")
      (node (ref "J1") (pin "B68") (pinfunction "B68_B68") (pintype "unspecified"))
    )
    (net (code "171") (name "unconnected-(J1-PadB69)") (class "Default")
      (node (ref "J1") (pin "B69") (pinfunction "B69_B69") (pintype "unspecified"))
    )
    (net (code "172") (name "unconnected-(J1-PadB70)") (class "Default")
      (node (ref "J1") (pin "B70") (pinfunction "B70_B70") (pintype "unspecified"))
    )
    (net (code "173") (name "unconnected-(J1-PadB71)") (class "Default")
      (node (ref "J1") (pin "B71") (pinfunction "B71_B71") (pintype "unspecified"))
    )
    (net (code "174") (name "unconnected-(J1-PadB72)") (class "Default")
      (node (ref "J1") (pin "B72") (pinfunction "B72_B72") (pintype "unspecified"))
    )
    (net (code "175") (name "unconnected-(J1-PadB73)") (class "Default")
      (node (ref "J1") (pin "B73") (pinfunction "B73_B73") (pintype "unspecified"))
    )
    (net (code "176") (name "unconnected-(J1-PadB74)") (class "Default")
      (node (ref "J1") (pin "B74") (pinfunction "B74_B74") (pintype "unspecified"))
    )
    (net (code "177") (name "unconnected-(J1-PadB75)") (class "Default")
      (node (ref "J1") (pin "B75") (pinfunction "B75_B75") (pintype "unspecified"))
    )
    (net (code "178") (name "unconnected-(J1-PadB76)") (class "Default")
      (node (ref "J1") (pin "B76") (pinfunction "B76_B76") (pintype "unspecified"))
    )
    (net (code "179") (name "unconnected-(J1-PadB77)") (class "Default")
      (node (ref "J1") (pin "B77") (pinfunction "B77_B77") (pintype "unspecified"))
    )
    (net (code "180") (name "unconnected-(J1-PadB78)") (class "Default")
      (node (ref "J1") (pin "B78") (pinfunction "B78_B78") (pintype "unspecified"))
    )
    (net (code "181") (name "unconnected-(J1-PadB79)") (class "Default")
      (node (ref "J1") (pin "B79") (pinfunction "B79_B79") (pintype "unspecified"))
    )
    (net (code "182") (name "unconnected-(J1-PadB80)") (class "Default")
      (node (ref "J1") (pin "B80") (pinfunction "B80_B80") (pintype "unspecified"))
    )
    (net (code "183") (name "unconnected-(J1-PadB81)") (class "Default")
      (node (ref "J1") (pin "B81") (pinfunction "B81_B81") (pintype "unspecified"))
    )
    (net (code "184") (name "unconnected-(J1-PadB82)") (class "Default")
      (node (ref "J1") (pin "B82") (pinfunction "B82_B82") (pintype "unspecified"))
    )
    (net (code "185") (name "unconnected-(U1-A0-Pad12)") (class "Default")
      (node (ref "U1") (pin "12") (pinfunction "A0_12") (pintype "unspecified"))
    )
    (net (code "186") (name "unconnected-(U1-A1-Pad11)") (class "Default")
      (node (ref "U1") (pin "11") (pinfunction "A1_11") (pintype "unspecified"))
    )
    (net (code "187") (name "unconnected-(U1-A2-Pad10)") (class "Default")
      (node (ref "U1") (pin "10") (pinfunction "A2_10") (pintype "unspecified"))
    )
    (net (code "188") (name "unconnected-(U1-A3-Pad9)") (class "Default")
      (node (ref "U1") (pin "9") (pinfunction "A3_9") (pintype "unspecified"))
    )
    (net (code "189") (name "unconnected-(U1-A4-Pad8)") (class "Default")
      (node (ref "U1") (pin "8") (pinfunction "A4_8") (pintype "unspecified"))
    )
    (net (code "190") (name "unconnected-(U1-A5-Pad7)") (class "Default")
      (node (ref "U1") (pin "7") (pinfunction "A5_7") (pintype "unspecified"))
    )
    (net (code "191") (name "unconnected-(U1-A6-Pad6)") (class "Default")
      (node (ref "U1") (pin "6") (pinfunction "A6_6") (pintype "unspecified"))
    )
    (net (code "192") (name "unconnected-(U1-A7-Pad5)") (class "Default")
      (node (ref "U1") (pin "5") (pinfunction "A7_5") (pintype "unspecified"))
    )
    (net (code "193") (name "unconnected-(U1-A8-Pad27)") (class "Default")
      (node (ref "U1") (pin "27") (pinfunction "A8_27") (pintype "unspecified"))
    )
    (net (code "194") (name "unconnected-(U1-A9-Pad26)") (class "Default")
      (node (ref "U1") (pin "26") (pinfunction "A9_26") (pintype "unspecified"))
    )
    (net (code "195") (name "unconnected-(U1-A10-Pad23)") (class "Default")
      (node (ref "U1") (pin "23") (pinfunction "A10_23") (pintype "unspecified"))
    )
    (net (code "196") (name "unconnected-(U1-A11-Pad25)") (class "Default")
      (node (ref "U1") (pin "25") (pinfunction "A11_25") (pintype "unspecified"))
    )
    (net (code "197") (name "unconnected-(U1-A12-Pad4)") (class "Default")
      (node (ref "U1") (pin "4") (pinfunction "A12_4") (pintype "unspecified"))
    )
    (net (code "198") (name "unconnected-(U1-A13-Pad28)") (class "Default")
      (node (ref "U1") (pin "28") (pinfunction "A13_28") (pintype "unspecified"))
    )
    (net (code "199") (name "unconnected-(U1-A14-Pad29)") (class "Default")
      (node (ref "U1") (pin "29") (pinfunction "A14_29") (pintype "unspecified"))
    )
    (net (code "200") (name "unconnected-(U1-A15-Pad3)") (class "Default")
      (node (ref "U1") (pin "3") (pinfunction "A15_3") (pintype "unspecified"))
    )
    (net (code "201") (name "unconnected-(U1-A17-Pad30)") (class "Default")
      (node (ref "U1") (pin "30") (pinfunction "A17_30") (pintype "unspecified"))
    )
    (net (code "202") (name "unconnected-(U1-A18-Pad1)") (class "Default")
      (node (ref "U1") (pin "1") (pinfunction "A18_1") (pintype "unspecified"))
    )
    (net (code "203") (name "unconnected-(U1-OE#-Pad24)") (class "Default")
      (node (ref "U1") (pin "24") (pinfunction "OE#_24") (pintype "unspecified"))
    )
    (net (code "204") (name "unconnected-(U1-WE#-Pad31)") (class "Default")
      (node (ref "U1") (pin "31") (pinfunction "WE#_31") (pintype "unspecified"))
    )
    (net (code "205") (name "unconnected-(U6-2A-Pad3)") (class "Default")
      (node (ref "U6") (pin "3") (pinfunction "2A_3") (pintype "unspecified"))
    )
    (net (code "206") (name "unconnected-(U6-2Y-Pad4)") (class "Default")
      (node (ref "U6") (pin "4") (pinfunction "2Y_4") (pintype "unspecified"))
    )
    (net (code "207") (name "unconnected-(U6-3A-Pad5)") (class "Default")
      (node (ref "U6") (pin "5") (pinfunction "3A_5") (pintype "unspecified"))
    )
    (net (code "208") (name "unconnected-(U6-3Y-Pad6)") (class "Default")
      (node (ref "U6") (pin "6") (pinfunction "3Y_6") (pintype "unspecified"))
    )
    (net (code "209") (name "unconnected-(U6-4A-Pad9)") (class "Default")
      (node (ref "U6") (pin "9") (pinfunction "4A_9") (pintype "unspecified"))
    )
    (net (code "210") (name "unconnected-(U6-4Y-Pad8)") (class "Default")
      (node (ref "U6") (pin "8") (pinfunction "4Y_8") (pintype "unspecified"))
    )
    (net (code "211") (name "unconnected-(U6-5A-Pad11)") (class "Default")
      (node (ref "U6") (pin "11") (pinfunction "5A_11") (pintype "unspecified"))
    )
    (net (code "212") (name "unconnected-(U6-5Y-Pad10)") (class "Default")
      (node (ref "U6") (pin "10") (pinfunction "5Y_10") (pintype "unspecified"))
    )
    (net (code "213") (name "unconnected-(U6-6A-Pad13)") (class "Default")
      (node (ref "U6") (pin "13") (pinfunction "6A_13") (pintype "unspecified"))
    )
    (net (code "214") (name "unconnected-(U6-6Y-Pad12)") (class "Default")
      (node (ref "U6") (pin "12") (pinfunction "6Y_12") (pintype "unspecified"))
    )
  )
)
